# CANBUSdataLoggerProjectFile.net
KiCad netlist of a schematic drawn in EasyEDA Pro
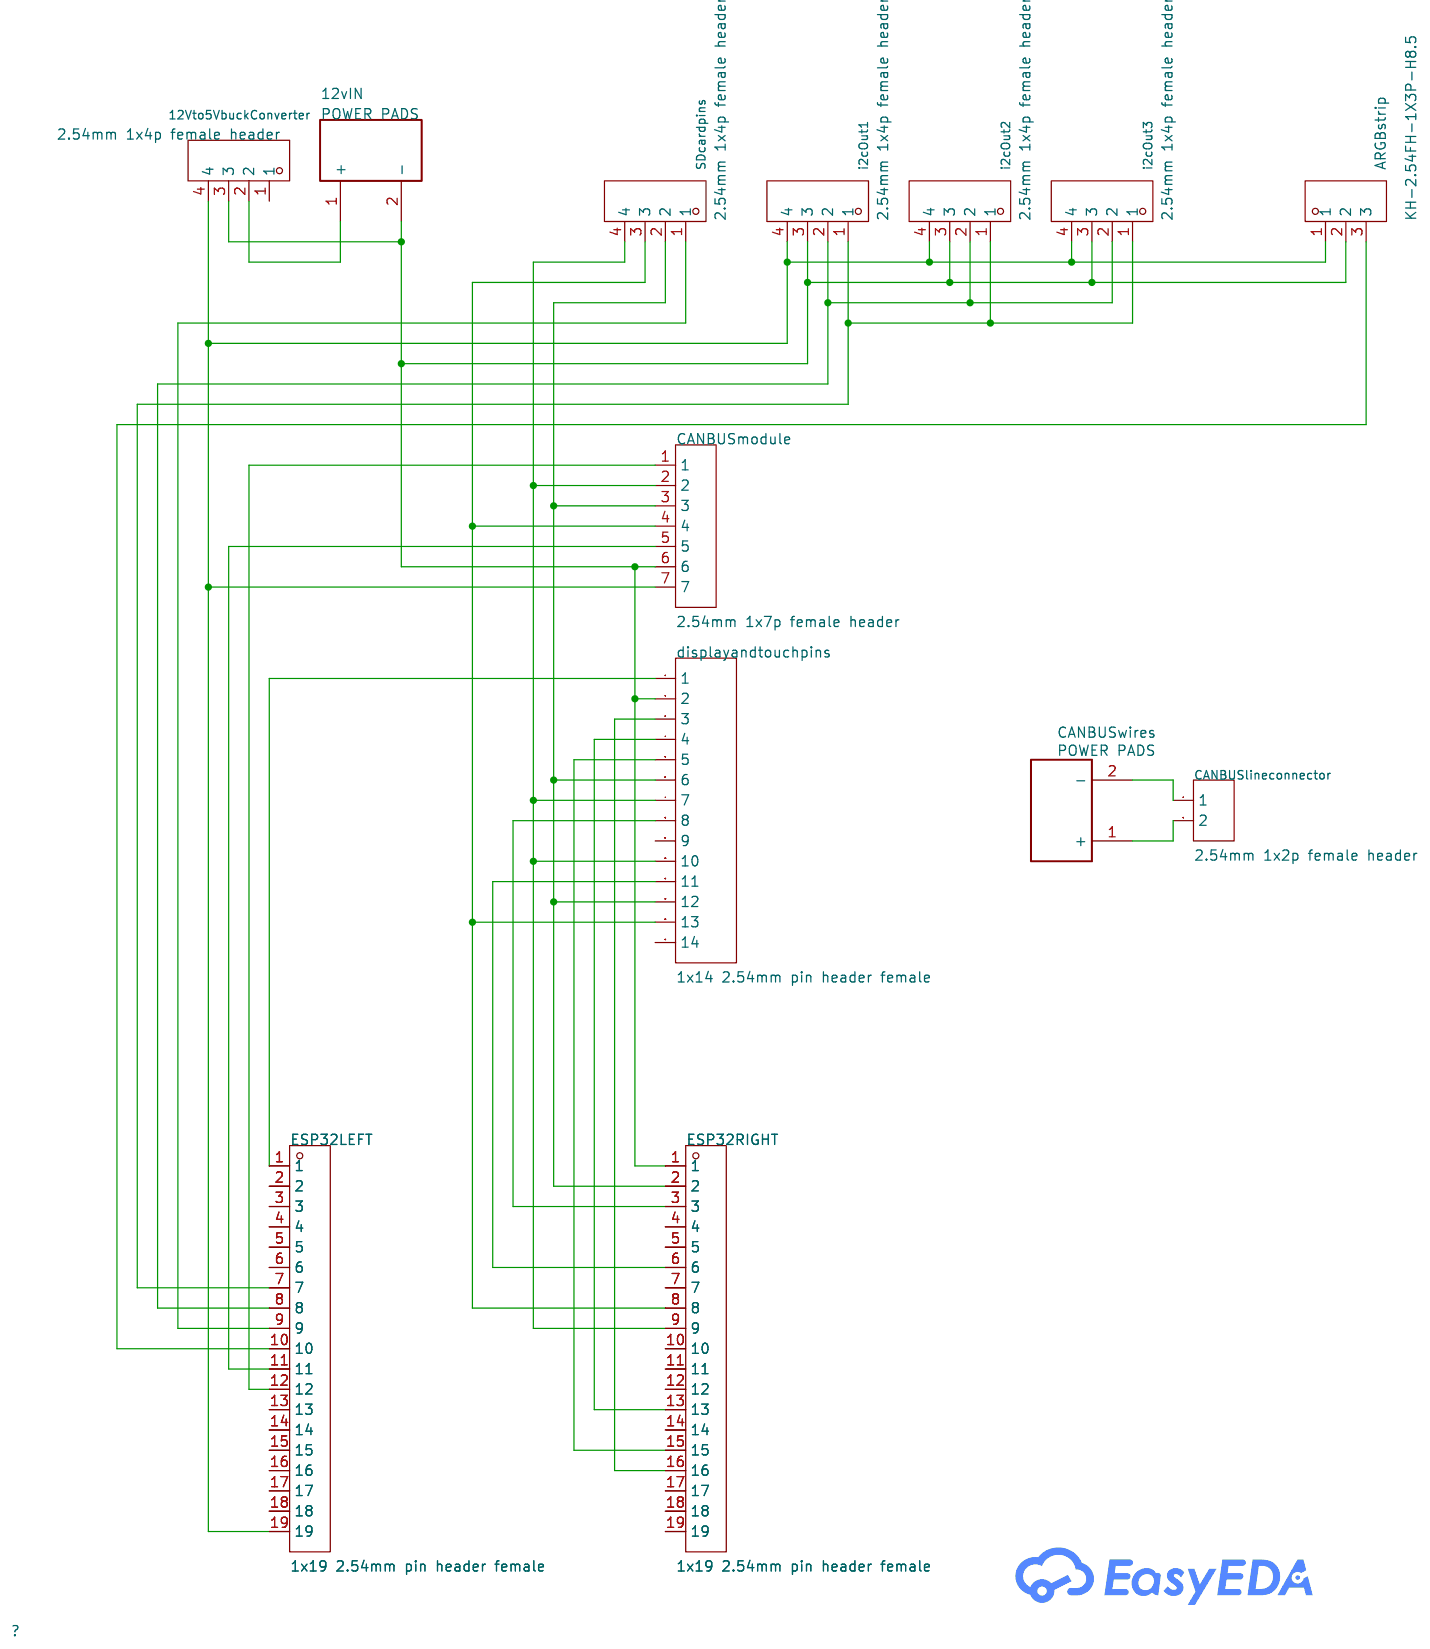
[diagram p0: schematic sheet]

(export (version "E")
  (design (tool "Eeschema 10.0.6"))
  (components
    (comp (ref "12vIN")
      (value "POWER PADS")
      (footprint "easyedapro:POWERPADS")
      (fields (field (name "Contributor") "tomicode"))
      (libsource (lib "easyedapro") (part "POWER PADS"))
    )
    (comp (ref "12Vto5VbuckConverter")
      (value "2.54mm 1x4p female header")
      (footprint "easyedapro:HDR-TH_4P-P2.54-V-F")
      (fields (field (name "Manufacturer") "BOOMELE(博穆精密)"))
      (libsource (lib "easyedapro") (part "2.54-1*4P母"))
    )
    (comp (ref "ARGBstrip")
      (value "KH-2.54FH-1X3P-H8.5")
      (footprint "easyedapro:HDR-TH_3P-P2.54-V-F")
      (fields (field (name "Manufacturer") "kinghelm(金航标)"))
      (libsource (lib "easyedapro") (part "KH-2.54FH-1X3P-H8.5"))
    )
    (comp (ref "CANBUSlineconnector")
      (value "2.54mm 1x2p female header")
      (footprint "easyedapro:HDR-TH_2P-P2.54-V-F")
      (fields (field (name "Manufacturer") "BOOMELE(博穆精密)"))
      (libsource (lib "easyedapro") (part "Header-Female-2.54_1x2"))
    )
    (comp (ref "CANBUSmodule")
      (value "2.54mm 1x7p female header")
      (footprint "easyedapro:HDR-TH_7P-P2.54-V-F")
      (fields (field (name "Manufacturer") "HC(虹成电子)"))
      (libsource (lib "easyedapro") (part "HC-PM254-8.5H-1X7PZ"))
    )
    (comp (ref "CANBUSwires")
      (value "POWER PADS")
      (footprint "easyedapro:POWERPADS")
      (fields (field (name "Contributor") "tomicode"))
      (libsource (lib "easyedapro") (part "POWER PADS"))
    )
    (comp (ref "displayandtouchpins")
      (value "1x14 2.54mm pin header female")
      (footprint "easyedapro:HDR-TH_14P-P2.54-V-F-1")
      (fields (field (name "Manufacturer") "BOOMELE(博穆精密)"))
      (libsource (lib "easyedapro") (part "Female header 2.54-1*14P"))
    )
    (comp (ref "ESP32LEFT")
      (value "1x19 2.54mm pin header female")
      (footprint "easyedapro:HDR-TH_19P-P2.54-V-F")
      (fields (field (name "Manufacturer") "kinghelm(金航标)"))
      (libsource (lib "easyedapro") (part "KH-2.54FH-1X19P-H8.5"))
    )
    (comp (ref "ESP32RIGHT")
      (value "1x19 2.54mm pin header female")
      (footprint "easyedapro:HDR-TH_19P-P2.54-V-F")
      (fields (field (name "Manufacturer") "kinghelm(金航标)"))
      (libsource (lib "easyedapro") (part "KH-2.54FH-1X19P-H8.5"))
    )
    (comp (ref "i2cOut1")
      (value "2.54mm 1x4p female header")
      (footprint "easyedapro:HDR-TH_4P-P2.54-V-F")
      (fields (field (name "Manufacturer") "BOOMELE(博穆精密)"))
      (libsource (lib "easyedapro") (part "2.54-1*4P母"))
    )
    (comp (ref "i2cOut2")
      (value "2.54mm 1x4p female header")
      (footprint "easyedapro:HDR-TH_4P-P2.54-V-F")
      (fields (field (name "Manufacturer") "BOOMELE(博穆精密)"))
      (libsource (lib "easyedapro") (part "2.54-1*4P母"))
    )
    (comp (ref "i2cOut3")
      (value "2.54mm 1x4p female header")
      (footprint "easyedapro:HDR-TH_4P-P2.54-V-F")
      (fields (field (name "Manufacturer") "BOOMELE(博穆精密)"))
      (libsource (lib "easyedapro") (part "2.54-1*4P母"))
    )
    (comp (ref "SDcardpins")
      (value "2.54mm 1x4p female header")
      (footprint "easyedapro:HDR-TH_4P-P2.54-V-F")
      (fields (field (name "Manufacturer") "BOOMELE(博穆精密)"))
      (libsource (lib "easyedapro") (part "2.54-1*4P母"))
    )
  )
  (nets
    (net (code "1") (name "Net-(12Vto5VbuckConverter-Pad4)") (class "Default")
      (node (ref "12Vto5VbuckConverter") (pin "4") (pinfunction "4_4") (pintype "input"))
      (node (ref "ARGBstrip") (pin "1") (pinfunction "1_1") (pintype "unspecified"))
      (node (ref "CANBUSmodule") (pin "7") (pinfunction "7_7") (pintype "unspecified"))
      (node (ref "ESP32LEFT") (pin "19") (pinfunction "19_19") (pintype "unspecified"))
      (node (ref "i2cOut1") (pin "4") (pinfunction "4_4") (pintype "input"))
      (node (ref "i2cOut2") (pin "4") (pinfunction "4_4") (pintype "input"))
      (node (ref "i2cOut3") (pin "4") (pinfunction "4_4") (pintype "input"))
    )
    (net (code "2") (name "Net-(12vIN-+)") (class "Default")
      (node (ref "12Vto5VbuckConverter") (pin "2") (pinfunction "2_2") (pintype "input"))
      (node (ref "12vIN") (pin "1") (pinfunction "+_1") (pintype "unspecified"))
    )
    (net (code "3") (name "Net-(12vIN--)") (class "Default")
      (node (ref "12Vto5VbuckConverter") (pin "3") (pinfunction "3_3") (pintype "input"))
      (node (ref "12vIN") (pin "2") (pinfunction "-_2") (pintype "unspecified"))
      (node (ref "ARGBstrip") (pin "2") (pinfunction "2_2") (pintype "unspecified"))
      (node (ref "CANBUSmodule") (pin "6") (pinfunction "6_6") (pintype "unspecified"))
      (node (ref "ESP32RIGHT") (pin "1") (pinfunction "1_1") (pintype "unspecified"))
      (node (ref "displayandtouchpins") (pin "2") (pinfunction "2_2") (pintype "input"))
      (node (ref "i2cOut1") (pin "3") (pinfunction "3_3") (pintype "input"))
      (node (ref "i2cOut2") (pin "3") (pinfunction "3_3") (pintype "input"))
      (node (ref "i2cOut3") (pin "3") (pinfunction "3_3") (pintype "input"))
    )
    (net (code "4") (name "Net-(ARGBstrip-Pad3)") (class "Default")
      (node (ref "ARGBstrip") (pin "3") (pinfunction "3_3") (pintype "unspecified"))
      (node (ref "ESP32LEFT") (pin "10") (pinfunction "10_10") (pintype "unspecified"))
    )
    (net (code "5") (name "Net-(CANBUSmodule-Pad1)") (class "Default")
      (node (ref "CANBUSmodule") (pin "1") (pinfunction "1_1") (pintype "unspecified"))
      (node (ref "ESP32LEFT") (pin "12") (pinfunction "12_12") (pintype "unspecified"))
    )
    (net (code "6") (name "Net-(CANBUSmodule-Pad2)") (class "Default")
      (node (ref "CANBUSmodule") (pin "2") (pinfunction "2_2") (pintype "unspecified"))
      (node (ref "ESP32RIGHT") (pin "9") (pinfunction "9_9") (pintype "unspecified"))
      (node (ref "SDcardpins") (pin "4") (pinfunction "4_4") (pintype "input"))
      (node (ref "displayandtouchpins") (pin "10") (pinfunction "10_10") (pintype "input"))
      (node (ref "displayandtouchpins") (pin "7") (pinfunction "7_7") (pintype "input"))
    )
    (net (code "7") (name "Net-(CANBUSmodule-Pad3)") (class "Default")
      (node (ref "CANBUSmodule") (pin "3") (pinfunction "3_3") (pintype "unspecified"))
      (node (ref "ESP32RIGHT") (pin "2") (pinfunction "2_2") (pintype "unspecified"))
      (node (ref "SDcardpins") (pin "2") (pinfunction "2_2") (pintype "input"))
      (node (ref "displayandtouchpins") (pin "12") (pinfunction "12_12") (pintype "input"))
      (node (ref "displayandtouchpins") (pin "6") (pinfunction "6_6") (pintype "input"))
    )
    (net (code "8") (name "Net-(CANBUSmodule-Pad4)") (class "Default")
      (node (ref "CANBUSmodule") (pin "4") (pinfunction "4_4") (pintype "unspecified"))
      (node (ref "ESP32RIGHT") (pin "8") (pinfunction "8_8") (pintype "unspecified"))
      (node (ref "SDcardpins") (pin "3") (pinfunction "3_3") (pintype "input"))
      (node (ref "displayandtouchpins") (pin "13") (pinfunction "13_13") (pintype "input"))
    )
    (net (code "9") (name "Net-(CANBUSmodule-Pad5)") (class "Default")
      (node (ref "CANBUSmodule") (pin "5") (pinfunction "5_5") (pintype "unspecified"))
      (node (ref "ESP32LEFT") (pin "11") (pinfunction "11_11") (pintype "unspecified"))
    )
    (net (code "10") (name "Net-(CANBUSwires-+)") (class "Default")
      (node (ref "CANBUSlineconnector") (pin "2") (pinfunction "2_2") (pintype "input"))
      (node (ref "CANBUSwires") (pin "1") (pinfunction "+_1") (pintype "unspecified"))
    )
    (net (code "11") (name "Net-(CANBUSwires--)") (class "Default")
      (node (ref "CANBUSlineconnector") (pin "1") (pinfunction "1_1") (pintype "input"))
      (node (ref "CANBUSwires") (pin "2") (pinfunction "-_2") (pintype "unspecified"))
    )
    (net (code "12") (name "Net-(ESP32LEFT-Pad1)") (class "Default")
      (node (ref "ESP32LEFT") (pin "1") (pinfunction "1_1") (pintype "unspecified"))
      (node (ref "displayandtouchpins") (pin "1") (pinfunction "1_1") (pintype "input"))
    )
    (net (code "13") (name "Net-(ESP32LEFT-Pad7)") (class "Default")
      (node (ref "ESP32LEFT") (pin "7") (pinfunction "7_7") (pintype "unspecified"))
      (node (ref "i2cOut1") (pin "1") (pinfunction "1_1") (pintype "input"))
      (node (ref "i2cOut2") (pin "1") (pinfunction "1_1") (pintype "input"))
      (node (ref "i2cOut3") (pin "1") (pinfunction "1_1") (pintype "input"))
    )
    (net (code "14") (name "Net-(ESP32LEFT-Pad8)") (class "Default")
      (node (ref "ESP32LEFT") (pin "8") (pinfunction "8_8") (pintype "unspecified"))
      (node (ref "i2cOut1") (pin "2") (pinfunction "2_2") (pintype "input"))
      (node (ref "i2cOut2") (pin "2") (pinfunction "2_2") (pintype "input"))
      (node (ref "i2cOut3") (pin "2") (pinfunction "2_2") (pintype "input"))
    )
    (net (code "15") (name "Net-(ESP32LEFT-Pad9)") (class "Default")
      (node (ref "ESP32LEFT") (pin "9") (pinfunction "9_9") (pintype "unspecified"))
      (node (ref "SDcardpins") (pin "1") (pinfunction "1_1") (pintype "input"))
    )
    (net (code "16") (name "Net-(ESP32RIGHT-Pad3)") (class "Default")
      (node (ref "ESP32RIGHT") (pin "3") (pinfunction "3_3") (pintype "unspecified"))
      (node (ref "displayandtouchpins") (pin "8") (pinfunction "8_8") (pintype "input"))
    )
    (net (code "17") (name "Net-(ESP32RIGHT-Pad6)") (class "Default")
      (node (ref "ESP32RIGHT") (pin "6") (pinfunction "6_6") (pintype "unspecified"))
      (node (ref "displayandtouchpins") (pin "11") (pinfunction "11_11") (pintype "input"))
    )
    (net (code "18") (name "Net-(ESP32RIGHT-Pad13)") (class "Default")
      (node (ref "ESP32RIGHT") (pin "13") (pinfunction "13_13") (pintype "unspecified"))
      (node (ref "displayandtouchpins") (pin "4") (pinfunction "4_4") (pintype "input"))
    )
    (net (code "19") (name "Net-(ESP32RIGHT-Pad15)") (class "Default")
      (node (ref "ESP32RIGHT") (pin "15") (pinfunction "15_15") (pintype "unspecified"))
      (node (ref "displayandtouchpins") (pin "5") (pinfunction "5_5") (pintype "input"))
    )
    (net (code "20") (name "Net-(ESP32RIGHT-Pad16)") (class "Default")
      (node (ref "ESP32RIGHT") (pin "16") (pinfunction "16_16") (pintype "unspecified"))
      (node (ref "displayandtouchpins") (pin "3") (pinfunction "3_3") (pintype "input"))
    )
    (net (code "21") (name "unconnected-(12Vto5VbuckConverter-Pad1)") (class "Default")
      (node (ref "12Vto5VbuckConverter") (pin "1") (pinfunction "1_1") (pintype "input"))
    )
    (net (code "22") (name "unconnected-(ESP32LEFT-Pad2)") (class "Default")
      (node (ref "ESP32LEFT") (pin "2") (pinfunction "2_2") (pintype "unspecified"))
    )
    (net (code "23") (name "unconnected-(ESP32LEFT-Pad3)") (class "Default")
      (node (ref "ESP32LEFT") (pin "3") (pinfunction "3_3") (pintype "unspecified"))
    )
    (net (code "24") (name "unconnected-(ESP32LEFT-Pad4)") (class "Default")
      (node (ref "ESP32LEFT") (pin "4") (pinfunction "4_4") (pintype "unspecified"))
    )
    (net (code "25") (name "unconnected-(ESP32LEFT-Pad5)") (class "Default")
      (node (ref "ESP32LEFT") (pin "5") (pinfunction "5_5") (pintype "unspecified"))
    )
    (net (code "26") (name "unconnected-(ESP32LEFT-Pad6)") (class "Default")
      (node (ref "ESP32LEFT") (pin "6") (pinfunction "6_6") (pintype "unspecified"))
    )
    (net (code "27") (name "unconnected-(ESP32LEFT-Pad13)") (class "Default")
      (node (ref "ESP32LEFT") (pin "13") (pinfunction "13_13") (pintype "unspecified"))
    )
    (net (code "28") (name "unconnected-(ESP32LEFT-Pad14)") (class "Default")
      (node (ref "ESP32LEFT") (pin "14") (pinfunction "14_14") (pintype "unspecified"))
    )
    (net (code "29") (name "unconnected-(ESP32LEFT-Pad15)") (class "Default")
      (node (ref "ESP32LEFT") (pin "15") (pinfunction "15_15") (pintype "unspecified"))
    )
    (net (code "30") (name "unconnected-(ESP32LEFT-Pad16)") (class "Default")
      (node (ref "ESP32LEFT") (pin "16") (pinfunction "16_16") (pintype "unspecified"))
    )
    (net (code "31") (name "unconnected-(ESP32LEFT-Pad17)") (class "Default")
      (node (ref "ESP32LEFT") (pin "17") (pinfunction "17_17") (pintype "unspecified"))
    )
    (net (code "32") (name "unconnected-(ESP32LEFT-Pad18)") (class "Default")
      (node (ref "ESP32LEFT") (pin "18") (pinfunction "18_18") (pintype "unspecified"))
    )
    (net (code "33") (name "unconnected-(ESP32RIGHT-Pad4)") (class "Default")
      (node (ref "ESP32RIGHT") (pin "4") (pinfunction "4_4") (pintype "unspecified"))
    )
    (net (code "34") (name "unconnected-(ESP32RIGHT-Pad5)") (class "Default")
      (node (ref "ESP32RIGHT") (pin "5") (pinfunction "5_5") (pintype "unspecified"))
    )
    (net (code "35") (name "unconnected-(ESP32RIGHT-Pad7)") (class "Default")
      (node (ref "ESP32RIGHT") (pin "7") (pinfunction "7_7") (pintype "unspecified"))
    )
    (net (code "36") (name "unconnected-(ESP32RIGHT-Pad10)") (class "Default")
      (node (ref "ESP32RIGHT") (pin "10") (pinfunction "10_10") (pintype "unspecified"))
    )
    (net (code "37") (name "unconnected-(ESP32RIGHT-Pad11)") (class "Default")
      (node (ref "ESP32RIGHT") (pin "11") (pinfunction "11_11") (pintype "unspecified"))
    )
    (net (code "38") (name "unconnected-(ESP32RIGHT-Pad12)") (class "Default")
      (node (ref "ESP32RIGHT") (pin "12") (pinfunction "12_12") (pintype "unspecified"))
    )
    (net (code "39") (name "unconnected-(ESP32RIGHT-Pad14)") (class "Default")
      (node (ref "ESP32RIGHT") (pin "14") (pinfunction "14_14") (pintype "unspecified"))
    )
    (net (code "40") (name "unconnected-(ESP32RIGHT-Pad17)") (class "Default")
      (node (ref "ESP32RIGHT") (pin "17") (pinfunction "17_17") (pintype "unspecified"))
    )
    (net (code "41") (name "unconnected-(ESP32RIGHT-Pad18)") (class "Default")
      (node (ref "ESP32RIGHT") (pin "18") (pinfunction "18_18") (pintype "unspecified"))
    )
    (net (code "42") (name "unconnected-(ESP32RIGHT-Pad19)") (class "Default")
      (node (ref "ESP32RIGHT") (pin "19") (pinfunction "19_19") (pintype "unspecified"))
    )
    (net (code "43") (name "unconnected-(displayandtouchpins-Pad9)") (class "Default")
      (node (ref "displayandtouchpins") (pin "9") (pinfunction "9_9") (pintype "input"))
    )
    (net (code "44") (name "unconnected-(displayandtouchpins-Pad14)") (class "Default")
      (node (ref "displayandtouchpins") (pin "14") (pinfunction "14_14") (pintype "input"))
    )
  )
)
